# r4.net
KiCad netlist of a schematic drawn in EAGLE
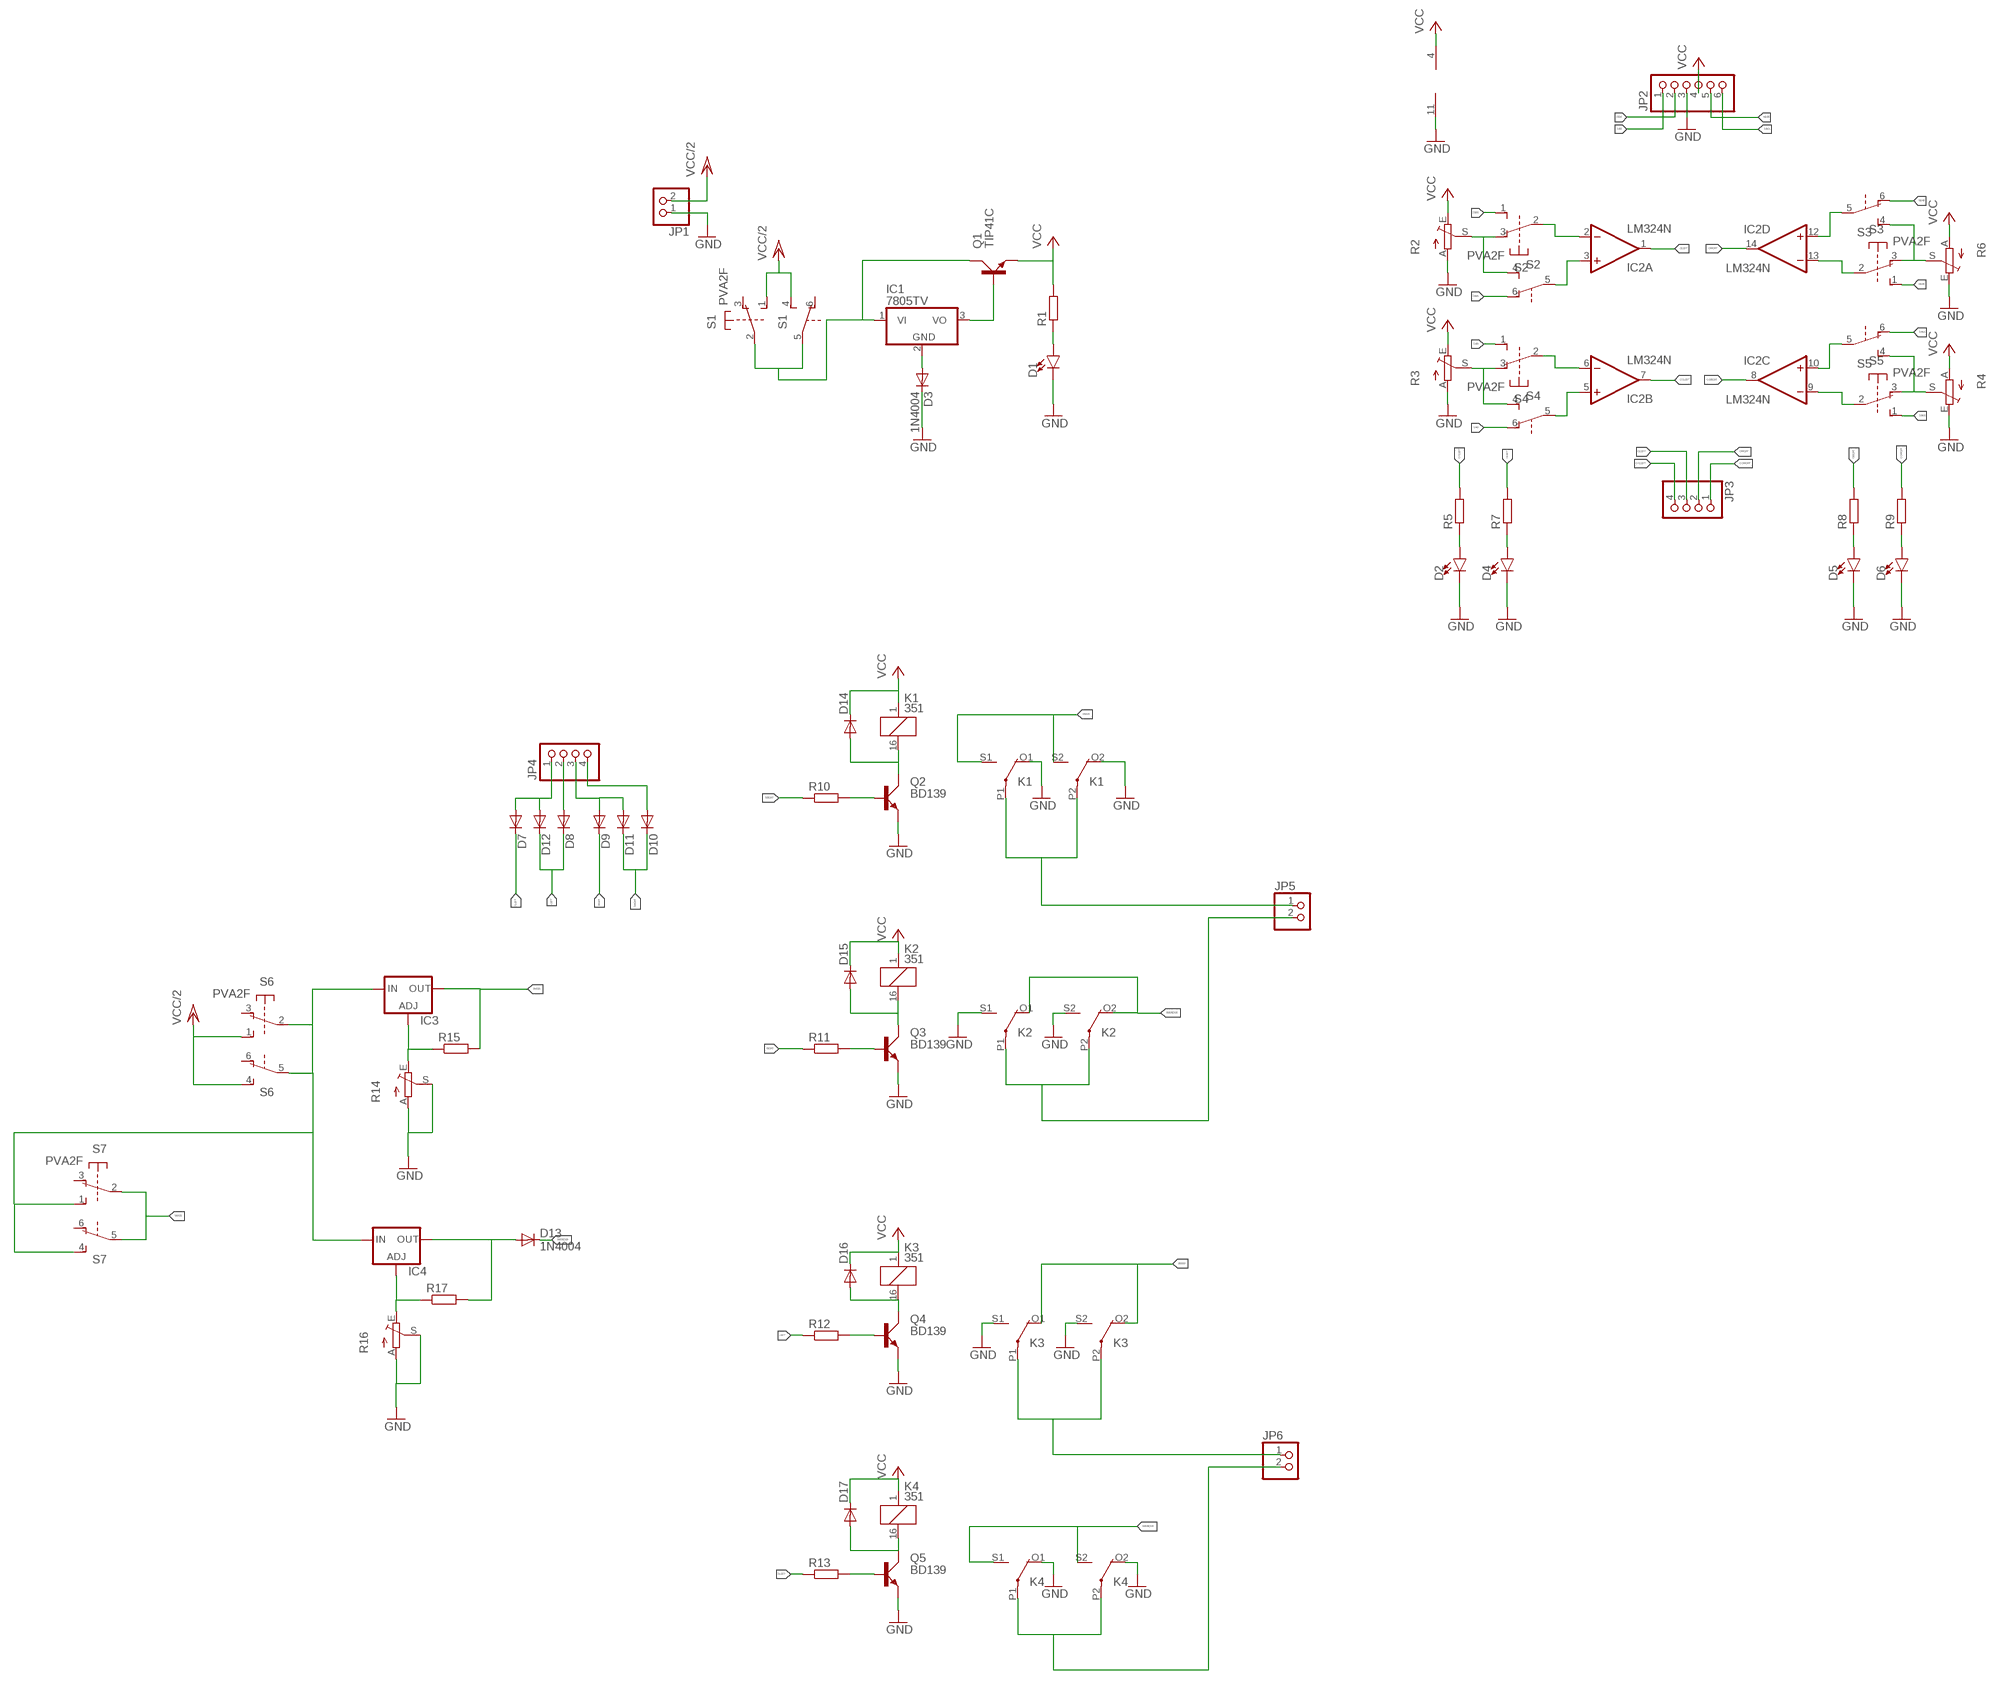
[diagram p0: schematic, sheet 1]

(export (version "E")
  (design (tool "Eeschema 10.0.6"))
  (components
    (comp (ref "D1")
      (value "LED5MM")
      (footprint "eagle-import:LED_5MM")
      (libsource (lib "eagle-import") (part "LED5MM"))
    )
    (comp (ref "D2")
      (value "LED5MM")
      (footprint "eagle-import:LED_5MM")
      (libsource (lib "eagle-import") (part "LED5MM"))
    )
    (comp (ref "D3")
      (value "1N4004")
      (footprint "eagle-import:DO41-10")
      (libsource (lib "eagle-import") (part "1N4004"))
    )
    (comp (ref "D4")
      (value "LED5MM")
      (footprint "eagle-import:LED_5MM")
      (libsource (lib "eagle-import") (part "LED5MM"))
    )
    (comp (ref "D5")
      (value "LED5MM")
      (footprint "eagle-import:LED_5MM")
      (libsource (lib "eagle-import") (part "LED5MM"))
    )
    (comp (ref "D6")
      (value "LED5MM")
      (footprint "eagle-import:LED_5MM")
      (libsource (lib "eagle-import") (part "LED5MM"))
    )
    (comp (ref "D7")
      (value "1N4148DO35-7")
      (footprint "eagle-import:DO35-7")
      (libsource (lib "eagle-import") (part "1N4148DO35-7"))
    )
    (comp (ref "D8")
      (value "1N4148DO35-7")
      (footprint "eagle-import:DO35-7")
      (libsource (lib "eagle-import") (part "1N4148DO35-7"))
    )
    (comp (ref "D9")
      (value "1N4148DO35-7")
      (footprint "eagle-import:DO35-7")
      (libsource (lib "eagle-import") (part "1N4148DO35-7"))
    )
    (comp (ref "D10")
      (value "1N4148DO35-7")
      (footprint "eagle-import:DO35-7")
      (libsource (lib "eagle-import") (part "1N4148DO35-7"))
    )
    (comp (ref "D11")
      (value "1N4148DO35-7")
      (footprint "eagle-import:DO35-7")
      (libsource (lib "eagle-import") (part "1N4148DO35-7"))
    )
    (comp (ref "D12")
      (value "1N4148DO35-7")
      (footprint "eagle-import:DO35-7")
      (libsource (lib "eagle-import") (part "1N4148DO35-7"))
    )
    (comp (ref "D13")
      (value "1N4004")
      (footprint "eagle-import:DO41-10")
      (libsource (lib "eagle-import") (part "1N4004"))
    )
    (comp (ref "D14")
      (value "1N4148DO35-7")
      (footprint "eagle-import:DO35-7")
      (libsource (lib "eagle-import") (part "1N4148DO35-7"))
    )
    (comp (ref "D15")
      (value "1N4148DO35-7")
      (footprint "eagle-import:DO35-7")
      (libsource (lib "eagle-import") (part "1N4148DO35-7"))
    )
    (comp (ref "D16")
      (value "1N4148DO35-7")
      (footprint "eagle-import:DO35-7")
      (libsource (lib "eagle-import") (part "1N4148DO35-7"))
    )
    (comp (ref "D17")
      (value "1N4148DO35-7")
      (footprint "eagle-import:DO35-7")
      (libsource (lib "eagle-import") (part "1N4148DO35-7"))
    )
    (comp (ref "IC1")
      (value "7805TV")
      (footprint "eagle-import:TO220V")
      (libsource (lib "eagle-import") (part "78TV05"))
    )
    (comp (ref "IC2")
      (value "LM324N")
      (footprint "eagle-import:DIL14")
      (libsource (lib "eagle-import") (part "LM324N"))
    )
    (comp (ref "IC3")
      (value "LM317TS")
      (footprint "eagle-import:317TS")
      (libsource (lib "eagle-import") (part "LM317TS"))
    )
    (comp (ref "IC4")
      (value "LM317TS")
      (footprint "eagle-import:317TS")
      (libsource (lib "eagle-import") (part "LM317TS"))
    )
    (comp (ref "JP1")
      (value "PINHD-1X2")
      (footprint "eagle-import:1X02")
      (libsource (lib "eagle-import") (part "PINHD-1X2"))
    )
    (comp (ref "JP2")
      (value "PINHD-1X6")
      (footprint "eagle-import:1X06")
      (libsource (lib "eagle-import") (part "PINHD-1X6"))
    )
    (comp (ref "JP3")
      (value "PINHD-1X4")
      (footprint "eagle-import:1X04")
      (libsource (lib "eagle-import") (part "PINHD-1X4"))
    )
    (comp (ref "JP4")
      (value "PINHD-1X4")
      (footprint "eagle-import:1X04")
      (libsource (lib "eagle-import") (part "PINHD-1X4"))
    )
    (comp (ref "JP5")
      (value "PINHD-1X2")
      (footprint "eagle-import:1X02")
      (libsource (lib "eagle-import") (part "PINHD-1X2"))
    )
    (comp (ref "JP6")
      (value "PINHD-1X2")
      (footprint "eagle-import:1X02")
      (libsource (lib "eagle-import") (part "PINHD-1X2"))
    )
    (comp (ref "K1")
      (value "351")
      (footprint "eagle-import:351")
      (libsource (lib "eagle-import") (part "351"))
    )
    (comp (ref "K2")
      (value "351")
      (footprint "eagle-import:351")
      (libsource (lib "eagle-import") (part "351"))
    )
    (comp (ref "K3")
      (value "351")
      (footprint "eagle-import:351")
      (libsource (lib "eagle-import") (part "351"))
    )
    (comp (ref "K4")
      (value "351")
      (footprint "eagle-import:351")
      (libsource (lib "eagle-import") (part "351"))
    )
    (comp (ref "Q1")
      (value "TIP41C")
      (footprint "eagle-import:TO220AV")
      (libsource (lib "eagle-import") (part "TIP41C"))
    )
    (comp (ref "Q2")
      (value "BD139")
      (footprint "eagle-import:TO126AV")
      (libsource (lib "eagle-import") (part "BD139"))
    )
    (comp (ref "Q3")
      (value "BD139")
      (footprint "eagle-import:TO126AV")
      (libsource (lib "eagle-import") (part "BD139"))
    )
    (comp (ref "Q4")
      (value "BD139")
      (footprint "eagle-import:TO126AV")
      (libsource (lib "eagle-import") (part "BD139"))
    )
    (comp (ref "Q5")
      (value "BD139")
      (footprint "eagle-import:TO126AV")
      (libsource (lib "eagle-import") (part "BD139"))
    )
    (comp (ref "R1")
      (value "R-EU_0204/7")
      (footprint "eagle-import:0204_7")
      (libsource (lib "eagle-import") (part "R-EU_0204/7"))
    )
    (comp (ref "R2")
      (value "TRIM_EU-CA6V")
      (footprint "eagle-import:CA6V")
      (libsource (lib "eagle-import") (part "TRIM_EU-CA6V"))
    )
    (comp (ref "R3")
      (value "TRIM_EU-CA6V")
      (footprint "eagle-import:CA6V")
      (libsource (lib "eagle-import") (part "TRIM_EU-CA6V"))
    )
    (comp (ref "R4")
      (value "TRIM_EU-CA6V")
      (footprint "eagle-import:CA6V")
      (libsource (lib "eagle-import") (part "TRIM_EU-CA6V"))
    )
    (comp (ref "R5")
      (value "R-EU_0204/7")
      (footprint "eagle-import:0204_7")
      (libsource (lib "eagle-import") (part "R-EU_0204/7"))
    )
    (comp (ref "R6")
      (value "TRIM_EU-CA6V")
      (footprint "eagle-import:CA6V")
      (libsource (lib "eagle-import") (part "TRIM_EU-CA6V"))
    )
    (comp (ref "R7")
      (value "R-EU_0204/7")
      (footprint "eagle-import:0204_7")
      (libsource (lib "eagle-import") (part "R-EU_0204/7"))
    )
    (comp (ref "R8")
      (value "R-EU_0204/7")
      (footprint "eagle-import:0204_7")
      (libsource (lib "eagle-import") (part "R-EU_0204/7"))
    )
    (comp (ref "R9")
      (value "R-EU_0204/7")
      (footprint "eagle-import:0204_7")
      (libsource (lib "eagle-import") (part "R-EU_0204/7"))
    )
    (comp (ref "R10")
      (value "R-EU_0204/7")
      (footprint "eagle-import:0204_7")
      (libsource (lib "eagle-import") (part "R-EU_0204/7"))
    )
    (comp (ref "R11")
      (value "R-EU_0204/7")
      (footprint "eagle-import:0204_7")
      (libsource (lib "eagle-import") (part "R-EU_0204/7"))
    )
    (comp (ref "R12")
      (value "R-EU_0204/7")
      (footprint "eagle-import:0204_7")
      (libsource (lib "eagle-import") (part "R-EU_0204/7"))
    )
    (comp (ref "R13")
      (value "R-EU_0204/7")
      (footprint "eagle-import:0204_7")
      (libsource (lib "eagle-import") (part "R-EU_0204/7"))
    )
    (comp (ref "R14")
      (value "TRIM_EU-CA6V")
      (footprint "eagle-import:CA6V")
      (libsource (lib "eagle-import") (part "TRIM_EU-CA6V"))
    )
    (comp (ref "R15")
      (value "R-EU_0204/7")
      (footprint "eagle-import:0204_7")
      (libsource (lib "eagle-import") (part "R-EU_0204/7"))
    )
    (comp (ref "R16")
      (value "TRIM_EU-CA6V")
      (footprint "eagle-import:CA6V")
      (libsource (lib "eagle-import") (part "TRIM_EU-CA6V"))
    )
    (comp (ref "R17")
      (value "R-EU_0204/7")
      (footprint "eagle-import:0204_7")
      (libsource (lib "eagle-import") (part "R-EU_0204/7"))
    )
    (comp (ref "S1")
      (value "PVA2F")
      (footprint "eagle-import:PVA2F")
      (libsource (lib "eagle-import") (part "PVA2F"))
    )
    (comp (ref "S2")
      (value "PVA2F")
      (footprint "eagle-import:PVA2F")
      (libsource (lib "eagle-import") (part "PVA2F"))
    )
    (comp (ref "S3")
      (value "PVA2F")
      (footprint "eagle-import:PVA2F")
      (libsource (lib "eagle-import") (part "PVA2F"))
    )
    (comp (ref "S4")
      (value "PVA2F")
      (footprint "eagle-import:PVA2F")
      (libsource (lib "eagle-import") (part "PVA2F"))
    )
    (comp (ref "S5")
      (value "PVA2F")
      (footprint "eagle-import:PVA2F")
      (libsource (lib "eagle-import") (part "PVA2F"))
    )
    (comp (ref "S6")
      (value "PVA2F")
      (footprint "eagle-import:PVA2F")
      (libsource (lib "eagle-import") (part "PVA2F"))
    )
    (comp (ref "S7")
      (value "PVA2F")
      (footprint "eagle-import:PVA2F")
      (libsource (lib "eagle-import") (part "PVA2F"))
    )
  )
  (nets
    (net (code "1") (name "DEKI") (class "Default")
      (node (ref "JP2") (pin "2") (pinfunction "2_2") (pintype "passive"))
      (node (ref "S2") (pin "1") (pinfunction "S_1") (pintype "passive"))
      (node (ref "S2") (pin "6") (pinfunction "O_6") (pintype "passive"))
    )
    (net (code "2") (name "GND") (class "Default")
      (node (ref "D1") (pin "K") (pinfunction "C_K") (pintype "passive"))
      (node (ref "D2") (pin "K") (pinfunction "C_K") (pintype "passive"))
      (node (ref "D3") (pin "C") (pinfunction "C_C") (pintype "passive"))
      (node (ref "D4") (pin "K") (pinfunction "C_K") (pintype "passive"))
      (node (ref "D5") (pin "K") (pinfunction "C_K") (pintype "passive"))
      (node (ref "D6") (pin "K") (pinfunction "C_K") (pintype "passive"))
      (node (ref "IC2") (pin "11") (pinfunction "V-_11") (pintype "power_in"))
      (node (ref "JP1") (pin "1") (pinfunction "1_1") (pintype "passive"))
      (node (ref "JP2") (pin "3") (pinfunction "3_3") (pintype "passive"))
      (node (ref "K1") (pin "O1") (pinfunction "O_O1") (pintype "passive"))
      (node (ref "K1") (pin "O2") (pinfunction "O_O2") (pintype "passive"))
      (node (ref "K2") (pin "S1") (pinfunction "S_S1") (pintype "passive"))
      (node (ref "K2") (pin "S2") (pinfunction "S_S2") (pintype "passive"))
      (node (ref "K3") (pin "S1") (pinfunction "S_S1") (pintype "passive"))
      (node (ref "K3") (pin "S2") (pinfunction "S_S2") (pintype "passive"))
      (node (ref "K4") (pin "O1") (pinfunction "O_O1") (pintype "passive"))
      (node (ref "K4") (pin "O2") (pinfunction "O_O2") (pintype "passive"))
      (node (ref "Q2") (pin "E") (pinfunction "E_E") (pintype "passive"))
      (node (ref "Q3") (pin "E") (pinfunction "E_E") (pintype "passive"))
      (node (ref "Q4") (pin "E") (pinfunction "E_E") (pintype "passive"))
      (node (ref "Q5") (pin "E") (pinfunction "E_E") (pintype "passive"))
      (node (ref "R14") (pin "A") (pinfunction "A_A") (pintype "passive"))
      (node (ref "R14") (pin "S") (pinfunction "S_S") (pintype "passive"))
      (node (ref "R16") (pin "A") (pinfunction "A_A") (pintype "passive"))
      (node (ref "R16") (pin "S") (pinfunction "S_S") (pintype "passive"))
      (node (ref "R2") (pin "A") (pinfunction "A_A") (pintype "passive"))
      (node (ref "R3") (pin "A") (pinfunction "A_A") (pintype "passive"))
      (node (ref "R4") (pin "E") (pinfunction "E_E") (pintype "passive"))
      (node (ref "R6") (pin "E") (pinfunction "E_E") (pintype "passive"))
    )
    (net (code "3") (name "LEFT") (class "Default")
      (node (ref "D12") (pin "C") (pinfunction "C_C") (pintype "passive"))
      (node (ref "D8") (pin "C") (pinfunction "C_C") (pintype "passive"))
      (node (ref "R12") (pin "1") (pinfunction "1_1") (pintype "passive"))
    )
    (net (code "4") (name "N$48") (class "Default")
      (node (ref "JP2") (pin "5") (pinfunction "5_5") (pintype "passive"))
      (node (ref "S3") (pin "1") (pinfunction "S_1") (pintype "passive"))
      (node (ref "S3") (pin "6") (pinfunction "O_6") (pintype "passive"))
    )
    (net (code "5") (name "Net-(D1-PadA)") (class "Default")
      (node (ref "D1") (pin "A") (pinfunction "A_A") (pintype "passive"))
      (node (ref "R1") (pin "1") (pinfunction "1_1") (pintype "passive"))
    )
    (net (code "6") (name "Net-(D2-PadA)") (class "Default")
      (node (ref "D2") (pin "A") (pinfunction "A_A") (pintype "passive"))
      (node (ref "R5") (pin "1") (pinfunction "1_1") (pintype "passive"))
    )
    (net (code "7") (name "Net-(D4-PadA)") (class "Default")
      (node (ref "D4") (pin "A") (pinfunction "A_A") (pintype "passive"))
      (node (ref "R7") (pin "1") (pinfunction "1_1") (pintype "passive"))
    )
    (net (code "8") (name "Net-(D5-PadA)") (class "Default")
      (node (ref "D5") (pin "A") (pinfunction "A_A") (pintype "passive"))
      (node (ref "R8") (pin "1") (pinfunction "1_1") (pintype "passive"))
    )
    (net (code "9") (name "Net-(D6-PadA)") (class "Default")
      (node (ref "D6") (pin "A") (pinfunction "A_A") (pintype "passive"))
      (node (ref "R9") (pin "1") (pinfunction "1_1") (pintype "passive"))
    )
    (net (code "10") (name "Net-(D8-PadA)") (class "Default")
      (node (ref "D8") (pin "A") (pinfunction "A_A") (pintype "passive"))
      (node (ref "JP4") (pin "2") (pinfunction "2_2") (pintype "passive"))
    )
    (net (code "11") (name "Net-(D10-PadA)") (class "Default")
      (node (ref "D10") (pin "A") (pinfunction "A_A") (pintype "passive"))
      (node (ref "JP4") (pin "4") (pinfunction "4_4") (pintype "passive"))
    )
    (net (code "12") (name "Net-(D11-PadA)") (class "Default")
      (node (ref "D11") (pin "A") (pinfunction "A_A") (pintype "passive"))
      (node (ref "D9") (pin "A") (pinfunction "A_A") (pintype "passive"))
      (node (ref "JP4") (pin "3") (pinfunction "3_3") (pintype "passive"))
    )
    (net (code "13") (name "Net-(D12-PadA)") (class "Default")
      (node (ref "D12") (pin "A") (pinfunction "A_A") (pintype "passive"))
      (node (ref "D7") (pin "A") (pinfunction "A_A") (pintype "passive"))
      (node (ref "JP4") (pin "1") (pinfunction "1_1") (pintype "passive"))
    )
    (net (code "14") (name "Net-(IC1-GND)") (class "Default")
      (node (ref "D3") (pin "A") (pinfunction "A_A") (pintype "passive"))
      (node (ref "IC1") (pin "2") (pinfunction "GND_2") (pintype "passive"))
    )
    (net (code "15") (name "Net-(IC1-VI)") (class "Default")
      (node (ref "IC1") (pin "1") (pinfunction "VI_1") (pintype "input"))
      (node (ref "Q1") (pin "C") (pinfunction "C_C") (pintype "passive"))
      (node (ref "S1") (pin "2") (pinfunction "P_2") (pintype "passive"))
      (node (ref "S1") (pin "5") (pinfunction "P_5") (pintype "passive"))
    )
    (net (code "16") (name "Net-(IC1-VO)") (class "Default")
      (node (ref "IC1") (pin "3") (pinfunction "VO_3") (pintype "passive"))
      (node (ref "Q1") (pin "B") (pinfunction "B_B") (pintype "passive"))
    )
    (net (code "17") (name "Net-(IC2A-+IN)") (class "Default")
      (node (ref "IC2") (pin "3") (pinfunction "+IN_3") (pintype "input"))
      (node (ref "S2") (pin "5") (pinfunction "P_5") (pintype "passive"))
    )
    (net (code "18") (name "Net-(IC2A--IN)") (class "Default")
      (node (ref "IC2") (pin "2") (pinfunction "-IN_2") (pintype "input"))
      (node (ref "S2") (pin "2") (pinfunction "P_2") (pintype "passive"))
    )
    (net (code "19") (name "Net-(IC2B-+IN)") (class "Default")
      (node (ref "IC2") (pin "5") (pinfunction "+IN_5") (pintype "input"))
      (node (ref "S4") (pin "5") (pinfunction "P_5") (pintype "passive"))
    )
    (net (code "20") (name "Net-(IC2B--IN)") (class "Default")
      (node (ref "IC2") (pin "6") (pinfunction "-IN_6") (pintype "input"))
      (node (ref "S4") (pin "2") (pinfunction "P_2") (pintype "passive"))
    )
    (net (code "21") (name "Net-(IC2C-+IN)") (class "Default")
      (node (ref "IC2") (pin "10") (pinfunction "+IN_10") (pintype "input"))
      (node (ref "S5") (pin "5") (pinfunction "P_5") (pintype "passive"))
    )
    (net (code "22") (name "Net-(IC2C--IN)") (class "Default")
      (node (ref "IC2") (pin "9") (pinfunction "-IN_9") (pintype "input"))
      (node (ref "S5") (pin "2") (pinfunction "P_2") (pintype "passive"))
    )
    (net (code "23") (name "Net-(IC2D-+IN)") (class "Default")
      (node (ref "IC2") (pin "12") (pinfunction "+IN_12") (pintype "input"))
      (node (ref "S3") (pin "5") (pinfunction "P_5") (pintype "passive"))
    )
    (net (code "24") (name "Net-(IC2D--IN)") (class "Default")
      (node (ref "IC2") (pin "13") (pinfunction "-IN_13") (pintype "input"))
      (node (ref "S3") (pin "2") (pinfunction "P_2") (pintype "passive"))
    )
    (net (code "25") (name "Net-(IC3-ADJ)") (class "Default")
      (node (ref "IC3") (pin "1") (pinfunction "ADJ_1") (pintype "input"))
      (node (ref "R14") (pin "E") (pinfunction "E_E") (pintype "passive"))
      (node (ref "R15") (pin "1") (pinfunction "1_1") (pintype "passive"))
    )
    (net (code "26") (name "Net-(IC3-IN)") (class "Default")
      (node (ref "IC3") (pin "3") (pinfunction "IN_3") (pintype "input"))
      (node (ref "IC4") (pin "3") (pinfunction "IN_3") (pintype "input"))
      (node (ref "S6") (pin "2") (pinfunction "P_2") (pintype "passive"))
      (node (ref "S6") (pin "5") (pinfunction "P_5") (pintype "passive"))
      (node (ref "S7") (pin "1") (pinfunction "S_1") (pintype "passive"))
      (node (ref "S7") (pin "4") (pinfunction "S_4") (pintype "passive"))
    )
    (net (code "27") (name "Net-(IC4-ADJ)") (class "Default")
      (node (ref "IC4") (pin "1") (pinfunction "ADJ_1") (pintype "input"))
      (node (ref "R16") (pin "E") (pinfunction "E_E") (pintype "passive"))
      (node (ref "R17") (pin "1") (pinfunction "1_1") (pintype "passive"))
    )
    (net (code "28") (name "Net-(IC4-OUT)") (class "Default")
      (node (ref "D13") (pin "A") (pinfunction "A_A") (pintype "passive"))
      (node (ref "IC4") (pin "2") (pinfunction "OUT_2") (pintype "passive"))
      (node (ref "R17") (pin "2") (pinfunction "2_2") (pintype "passive"))
    )
    (net (code "29") (name "Net-(K1A-2)") (class "Default")
      (node (ref "D14") (pin "A") (pinfunction "A_A") (pintype "passive"))
      (node (ref "K1") (pin "16") (pinfunction "2_16") (pintype "passive"))
      (node (ref "Q2") (pin "C") (pinfunction "C_C") (pintype "passive"))
    )
    (net (code "30") (name "Net-(K1B-P)") (class "Default")
      (node (ref "JP5") (pin "1") (pinfunction "1_1") (pintype "passive"))
      (node (ref "K1") (pin "P1") (pinfunction "P_P1") (pintype "passive"))
      (node (ref "K1") (pin "P2") (pinfunction "P_P2") (pintype "passive"))
    )
    (net (code "31") (name "Net-(K2A-2)") (class "Default")
      (node (ref "D15") (pin "A") (pinfunction "A_A") (pintype "passive"))
      (node (ref "K2") (pin "16") (pinfunction "2_16") (pintype "passive"))
      (node (ref "Q3") (pin "C") (pinfunction "C_C") (pintype "passive"))
    )
    (net (code "32") (name "Net-(K2B-P)") (class "Default")
      (node (ref "JP5") (pin "2") (pinfunction "2_2") (pintype "passive"))
      (node (ref "K2") (pin "P1") (pinfunction "P_P1") (pintype "passive"))
      (node (ref "K2") (pin "P2") (pinfunction "P_P2") (pintype "passive"))
    )
    (net (code "33") (name "Net-(K3A-2)") (class "Default")
      (node (ref "D16") (pin "A") (pinfunction "A_A") (pintype "passive"))
      (node (ref "K3") (pin "16") (pinfunction "2_16") (pintype "passive"))
      (node (ref "Q4") (pin "C") (pinfunction "C_C") (pintype "passive"))
    )
    (net (code "34") (name "Net-(K3B-P)") (class "Default")
      (node (ref "JP6") (pin "1") (pinfunction "1_1") (pintype "passive"))
      (node (ref "K3") (pin "P1") (pinfunction "P_P1") (pintype "passive"))
      (node (ref "K3") (pin "P2") (pinfunction "P_P2") (pintype "passive"))
    )
    (net (code "35") (name "Net-(K4A-2)") (class "Default")
      (node (ref "D17") (pin "A") (pinfunction "A_A") (pintype "passive"))
      (node (ref "K4") (pin "16") (pinfunction "2_16") (pintype "passive"))
      (node (ref "Q5") (pin "C") (pinfunction "C_C") (pintype "passive"))
    )
    (net (code "36") (name "Net-(K4B-P)") (class "Default")
      (node (ref "JP6") (pin "2") (pinfunction "2_2") (pintype "passive"))
      (node (ref "K4") (pin "P1") (pinfunction "P_P1") (pintype "passive"))
      (node (ref "K4") (pin "P2") (pinfunction "P_P2") (pintype "passive"))
    )
    (net (code "37") (name "Net-(Q2-PadB)") (class "Default")
      (node (ref "Q2") (pin "B") (pinfunction "B_B") (pintype "passive"))
      (node (ref "R10") (pin "2") (pinfunction "2_2") (pintype "passive"))
    )
    (net (code "38") (name "Net-(Q3-PadB)") (class "Default")
      (node (ref "Q3") (pin "B") (pinfunction "B_B") (pintype "passive"))
      (node (ref "R11") (pin "2") (pinfunction "2_2") (pintype "passive"))
    )
    (net (code "39") (name "Net-(Q4-PadB)") (class "Default")
      (node (ref "Q4") (pin "B") (pinfunction "B_B") (pintype "passive"))
      (node (ref "R12") (pin "2") (pinfunction "2_2") (pintype "passive"))
    )
    (net (code "40") (name "Net-(Q5-PadB)") (class "Default")
      (node (ref "Q5") (pin "B") (pinfunction "B_B") (pintype "passive"))
      (node (ref "R13") (pin "2") (pinfunction "2_2") (pintype "passive"))
    )
    (net (code "41") (name "Net-(S2A-O)") (class "Default")
      (node (ref "R2") (pin "S") (pinfunction "S_S") (pintype "passive"))
      (node (ref "S2") (pin "3") (pinfunction "O_3") (pintype "passive"))
      (node (ref "S2") (pin "4") (pinfunction "S_4") (pintype "passive"))
    )
    (net (code "42") (name "Net-(S3A-O)") (class "Default")
      (node (ref "R6") (pin "S") (pinfunction "S_S") (pintype "passive"))
      (node (ref "S3") (pin "3") (pinfunction "O_3") (pintype "passive"))
      (node (ref "S3") (pin "4") (pinfunction "S_4") (pintype "passive"))
    )
    (net (code "43") (name "Net-(S4A-O)") (class "Default")
      (node (ref "R3") (pin "S") (pinfunction "S_S") (pintype "passive"))
      (node (ref "S4") (pin "3") (pinfunction "O_3") (pintype "passive"))
      (node (ref "S4") (pin "4") (pinfunction "S_4") (pintype "passive"))
    )
    (net (code "44") (name "Net-(S5A-O)") (class "Default")
      (node (ref "R4") (pin "S") (pinfunction "S_S") (pintype "passive"))
      (node (ref "S5") (pin "3") (pinfunction "O_3") (pintype "passive"))
      (node (ref "S5") (pin "4") (pinfunction "S_4") (pintype "passive"))
    )
    (net (code "45") (name "OLEFT") (class "Default")
      (node (ref "IC2") (pin "1") (pinfunction "OUT_1") (pintype "output"))
      (node (ref "JP3") (pin "3") (pinfunction "3_3") (pintype "passive"))
      (node (ref "R7") (pin "2") (pinfunction "2_2") (pintype "passive"))
    )
    (net (code "46") (name "ORIGHT") (class "Default")
      (node (ref "IC2") (pin "14") (pinfunction "OUT_14") (pintype "output"))
      (node (ref "JP3") (pin "2") (pinfunction "2_2") (pintype "passive"))
      (node (ref "R8") (pin "2") (pinfunction "2_2") (pintype "passive"))
    )
    (net (code "47") (name "OSLEFT") (class "Default")
      (node (ref "IC2") (pin "7") (pinfunction "OUT_7") (pintype "output"))
      (node (ref "JP3") (pin "4") (pinfunction "4_4") (pintype "passive"))
      (node (ref "R5") (pin "2") (pinfunction "2_2") (pintype "passive"))
    )
    (net (code "48") (name "OSRIGHT") (class "Default")
      (node (ref "IC2") (pin "8") (pinfunction "OUT_8") (pintype "output"))
      (node (ref "JP3") (pin "1") (pinfunction "1_1") (pintype "passive"))
      (node (ref "R9") (pin "2") (pinfunction "2_2") (pintype "passive"))
    )
    (net (code "49") (name "RIGHT") (class "Default")
      (node (ref "D9") (pin "C") (pinfunction "C_C") (pintype "passive"))
      (node (ref "R11") (pin "1") (pinfunction "1_1") (pintype "passive"))
    )
    (net (code "50") (name "SAKA") (class "Default")
      (node (ref "JP2") (pin "6") (pinfunction "6_6") (pintype "passive"))
      (node (ref "S5") (pin "1") (pinfunction "S_1") (pintype "passive"))
      (node (ref "S5") (pin "6") (pinfunction "O_6") (pintype "passive"))
    )
    (net (code "51") (name "SAKI") (class "Default")
      (node (ref "JP2") (pin "1") (pinfunction "1_1") (pintype "passive"))
      (node (ref "S4") (pin "1") (pinfunction "S_1") (pintype "passive"))
      (node (ref "S4") (pin "6") (pinfunction "O_6") (pintype "passive"))
    )
    (net (code "52") (name "SLEFT") (class "Default")
      (node (ref "D7") (pin "C") (pinfunction "C_C") (pintype "passive"))
      (node (ref "R13") (pin "1") (pinfunction "1_1") (pintype "passive"))
    )
    (net (code "53") (name "SRIGHT") (class "Default")
      (node (ref "D10") (pin "C") (pinfunction "C_C") (pintype "passive"))
      (node (ref "D11") (pin "C") (pinfunction "C_C") (pintype "passive"))
      (node (ref "R10") (pin "1") (pinfunction "1_1") (pintype "passive"))
    )
    (net (code "54") (name "VCC") (class "Default")
      (node (ref "D14") (pin "C") (pinfunction "C_C") (pintype "passive"))
      (node (ref "D15") (pin "C") (pinfunction "C_C") (pintype "passive"))
      (node (ref "D16") (pin "C") (pinfunction "C_C") (pintype "passive"))
      (node (ref "D17") (pin "C") (pinfunction "C_C") (pintype "passive"))
      (node (ref "IC2") (pin "4") (pinfunction "V+_4") (pintype "power_in"))
      (node (ref "JP2") (pin "4") (pinfunction "4_4") (pintype "passive"))
      (node (ref "K1") (pin "1") (pinfunction "1_1") (pintype "passive"))
      (node (ref "K2") (pin "1") (pinfunction "1_1") (pintype "passive"))
      (node (ref "K3") (pin "1") (pinfunction "1_1") (pintype "passive"))
      (node (ref "K4") (pin "1") (pinfunction "1_1") (pintype "passive"))
      (node (ref "Q1") (pin "E") (pinfunction "E_E") (pintype "passive"))
      (node (ref "R1") (pin "2") (pinfunction "2_2") (pintype "passive"))
      (node (ref "R2") (pin "E") (pinfunction "E_E") (pintype "passive"))
      (node (ref "R3") (pin "E") (pinfunction "E_E") (pintype "passive"))
      (node (ref "R4") (pin "A") (pinfunction "A_A") (pintype "passive"))
      (node (ref "R6") (pin "A") (pinfunction "A_A") (pintype "passive"))
    )
    (net (code "55") (name "VCC{slash}2") (class "Default")
      (node (ref "JP1") (pin "2") (pinfunction "2_2") (pintype "passive"))
      (node (ref "S1") (pin "1") (pinfunction "S_1") (pintype "passive"))
      (node (ref "S1") (pin "4") (pinfunction "S_4") (pintype "passive"))
      (node (ref "S6") (pin "1") (pinfunction "S_1") (pintype "passive"))
      (node (ref "S6") (pin "4") (pinfunction "S_4") (pintype "passive"))
    )
    (net (code "56") (name "VMAJU") (class "Default")
      (node (ref "IC3") (pin "2") (pinfunction "OUT_2") (pintype "passive"))
      (node (ref "K1") (pin "S1") (pinfunction "S_S1") (pintype "passive"))
      (node (ref "K1") (pin "S2") (pinfunction "S_S2") (pintype "passive"))
      (node (ref "K3") (pin "O1") (pinfunction "O_O1") (pintype "passive"))
      (node (ref "K3") (pin "O2") (pinfunction "O_O2") (pintype "passive"))
      (node (ref "R15") (pin "2") (pinfunction "2_2") (pintype "passive"))
      (node (ref "S7") (pin "2") (pinfunction "P_2") (pintype "passive"))
      (node (ref "S7") (pin "5") (pinfunction "P_5") (pintype "passive"))
    )
    (net (code "57") (name "VMUNDUR") (class "Default")
      (node (ref "D13") (pin "C") (pinfunction "C_C") (pintype "passive"))
      (node (ref "K2") (pin "O1") (pinfunction "O_O1") (pintype "passive"))
      (node (ref "K2") (pin "O2") (pinfunction "O_O2") (pintype "passive"))
      (node (ref "K4") (pin "S1") (pinfunction "S_S1") (pintype "passive"))
      (node (ref "K4") (pin "S2") (pinfunction "S_S2") (pintype "passive"))
    )
    (net (code "58") (name "unconnected-(S1A-O-Pad3)") (class "Default")
      (node (ref "S1") (pin "3") (pinfunction "O_3") (pintype "passive"))
    )
    (net (code "59") (name "unconnected-(S1B-O-Pad6)") (class "Default")
      (node (ref "S1") (pin "6") (pinfunction "O_6") (pintype "passive"))
    )
    (net (code "60") (name "unconnected-(S6A-O-Pad3)") (class "Default")
      (node (ref "S6") (pin "3") (pinfunction "O_3") (pintype "passive"))
    )
    (net (code "61") (name "unconnected-(S6B-O-Pad6)") (class "Default")
      (node (ref "S6") (pin "6") (pinfunction "O_6") (pintype "passive"))
    )
    (net (code "62") (name "unconnected-(S7A-O-Pad3)") (class "Default")
      (node (ref "S7") (pin "3") (pinfunction "O_3") (pintype "passive"))
    )
    (net (code "63") (name "unconnected-(S7B-O-Pad6)") (class "Default")
      (node (ref "S7") (pin "6") (pinfunction "O_6") (pintype "passive"))
    )
  )
)
